# MODUL_GNU-BO_BRIDGE_V101.net
KiCad netlist of a schematic drawn in EAGLE
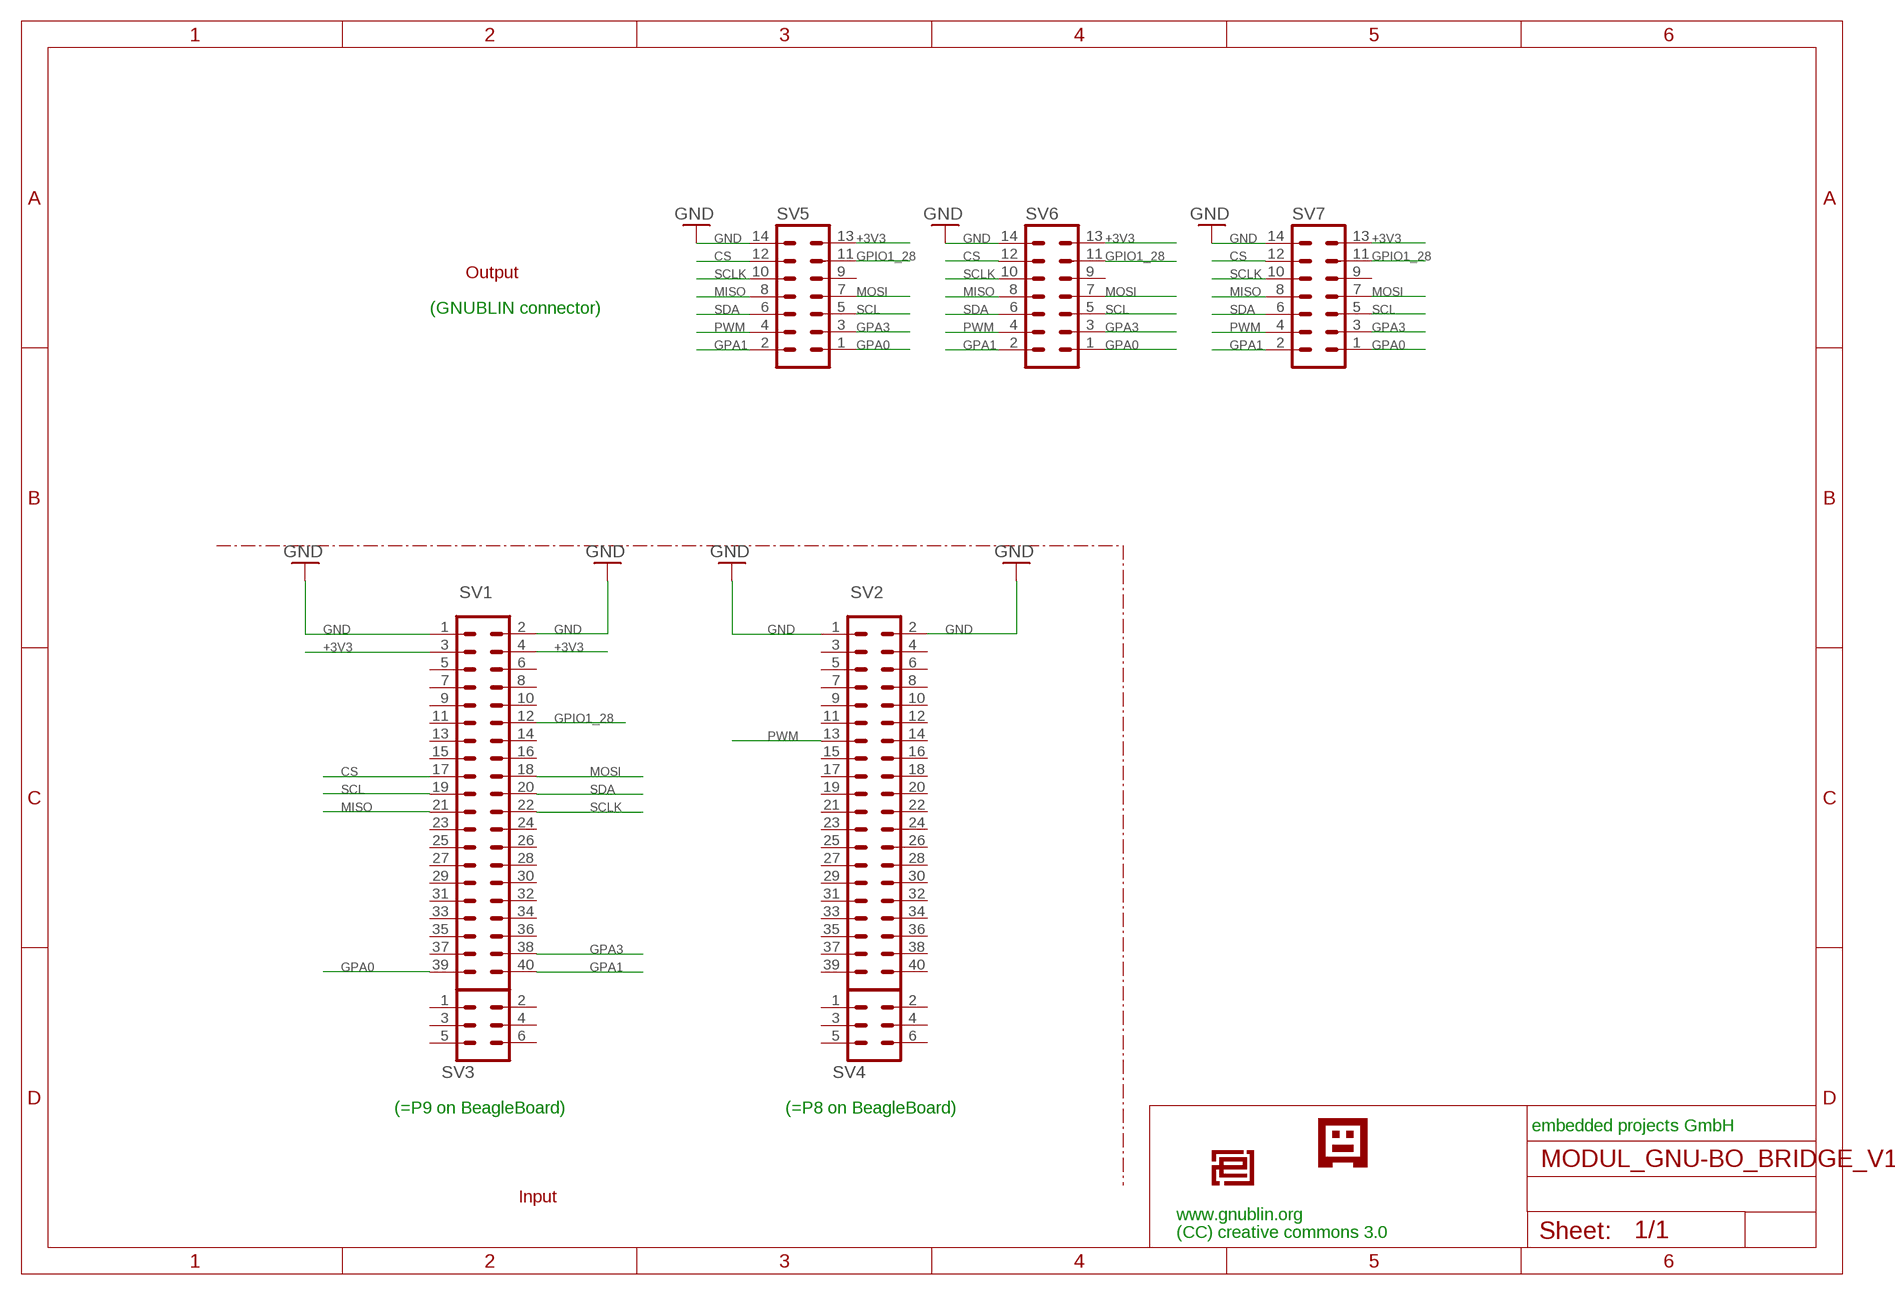
[diagram p0: schematic, sheet 1]

(export (version "E")
  (design (tool "Eeschema 10.0.6"))
  (components
    (comp (ref "SV1")
      (value "MA20-2")
      (footprint "eagle-import:MA20-2")
      (libsource (lib "eagle-import") (part "MA20-2"))
    )
    (comp (ref "SV2")
      (value "MA20-2")
      (footprint "eagle-import:MA20-2")
      (libsource (lib "eagle-import") (part "MA20-2"))
    )
    (comp (ref "SV3")
      (value "MA03-2")
      (footprint "eagle-import:MA03-2")
      (libsource (lib "eagle-import") (part "MA03-2"))
    )
    (comp (ref "SV4")
      (value "MA03-2")
      (footprint "eagle-import:MA03-2")
      (libsource (lib "eagle-import") (part "MA03-2"))
    )
    (comp (ref "SV5")
      (value "ML14")
      (footprint "eagle-import:ML14")
      (libsource (lib "eagle-import") (part "ML14"))
    )
    (comp (ref "SV6")
      (value "ML14")
      (footprint "eagle-import:ML14")
      (libsource (lib "eagle-import") (part "ML14"))
    )
    (comp (ref "SV7")
      (value "ML14")
      (footprint "eagle-import:ML14")
      (libsource (lib "eagle-import") (part "ML14"))
    )
    (comp (ref "U$2")
      (value "EPLOGOSIEB")
      (footprint "eagle-import:EPLOGOSIEBDRUCK")
      (libsource (lib "eagle-import") (part "EPLOGOSIEB"))
    )
    (comp (ref "U$3")
      (value "GNUBLINLOGOSIEB")
      (footprint "eagle-import:GNUSIEBDRUCK")
      (libsource (lib "eagle-import") (part "GNUBLINLOGOSIEB"))
    )
  )
  (nets
    (net (code "1") (name "/+3V3") (class "Default")
      (node (ref "SV1") (pin "3") (pinfunction "3_3") (pintype "passive"))
      (node (ref "SV1") (pin "4") (pinfunction "4_4") (pintype "passive"))
      (node (ref "SV5") (pin "13") (pinfunction "13_13") (pintype "passive"))
      (node (ref "SV6") (pin "13") (pinfunction "13_13") (pintype "passive"))
      (node (ref "SV7") (pin "13") (pinfunction "13_13") (pintype "passive"))
    )
    (net (code "2") (name "/CS") (class "Default")
      (node (ref "SV1") (pin "17") (pinfunction "17_17") (pintype "passive"))
      (node (ref "SV5") (pin "12") (pinfunction "12_12") (pintype "passive"))
      (node (ref "SV6") (pin "12") (pinfunction "12_12") (pintype "passive"))
      (node (ref "SV7") (pin "12") (pinfunction "12_12") (pintype "passive"))
    )
    (net (code "3") (name "/GPA0") (class "Default")
      (node (ref "SV1") (pin "39") (pinfunction "39_39") (pintype "passive"))
      (node (ref "SV5") (pin "1") (pinfunction "1_1") (pintype "passive"))
      (node (ref "SV6") (pin "1") (pinfunction "1_1") (pintype "passive"))
      (node (ref "SV7") (pin "1") (pinfunction "1_1") (pintype "passive"))
    )
    (net (code "4") (name "/GPA1") (class "Default")
      (node (ref "SV1") (pin "40") (pinfunction "40_40") (pintype "passive"))
      (node (ref "SV5") (pin "2") (pinfunction "2_2") (pintype "passive"))
      (node (ref "SV6") (pin "2") (pinfunction "2_2") (pintype "passive"))
      (node (ref "SV7") (pin "2") (pinfunction "2_2") (pintype "passive"))
    )
    (net (code "5") (name "/GPA3") (class "Default")
      (node (ref "SV1") (pin "38") (pinfunction "38_38") (pintype "passive"))
      (node (ref "SV5") (pin "3") (pinfunction "3_3") (pintype "passive"))
      (node (ref "SV6") (pin "3") (pinfunction "3_3") (pintype "passive"))
      (node (ref "SV7") (pin "3") (pinfunction "3_3") (pintype "passive"))
    )
    (net (code "6") (name "/GPIO1_28") (class "Default")
      (node (ref "SV1") (pin "12") (pinfunction "12_12") (pintype "passive"))
      (node (ref "SV5") (pin "11") (pinfunction "11_11") (pintype "passive"))
      (node (ref "SV6") (pin "11") (pinfunction "11_11") (pintype "passive"))
      (node (ref "SV7") (pin "11") (pinfunction "11_11") (pintype "passive"))
    )
    (net (code "7") (name "/MISO") (class "Default")
      (node (ref "SV1") (pin "21") (pinfunction "21_21") (pintype "passive"))
      (node (ref "SV5") (pin "8") (pinfunction "8_8") (pintype "passive"))
      (node (ref "SV6") (pin "8") (pinfunction "8_8") (pintype "passive"))
      (node (ref "SV7") (pin "8") (pinfunction "8_8") (pintype "passive"))
    )
    (net (code "8") (name "/MOSI") (class "Default")
      (node (ref "SV1") (pin "18") (pinfunction "18_18") (pintype "passive"))
      (node (ref "SV5") (pin "7") (pinfunction "7_7") (pintype "passive"))
      (node (ref "SV6") (pin "7") (pinfunction "7_7") (pintype "passive"))
      (node (ref "SV7") (pin "7") (pinfunction "7_7") (pintype "passive"))
    )
    (net (code "9") (name "/PWM") (class "Default")
      (node (ref "SV2") (pin "13") (pinfunction "13_13") (pintype "passive"))
      (node (ref "SV5") (pin "4") (pinfunction "4_4") (pintype "passive"))
      (node (ref "SV6") (pin "4") (pinfunction "4_4") (pintype "passive"))
      (node (ref "SV7") (pin "4") (pinfunction "4_4") (pintype "passive"))
    )
    (net (code "10") (name "/SCL") (class "Default")
      (node (ref "SV1") (pin "19") (pinfunction "19_19") (pintype "passive"))
      (node (ref "SV5") (pin "5") (pinfunction "5_5") (pintype "passive"))
      (node (ref "SV6") (pin "5") (pinfunction "5_5") (pintype "passive"))
      (node (ref "SV7") (pin "5") (pinfunction "5_5") (pintype "passive"))
    )
    (net (code "11") (name "/SCLK") (class "Default")
      (node (ref "SV1") (pin "22") (pinfunction "22_22") (pintype "passive"))
      (node (ref "SV5") (pin "10") (pinfunction "10_10") (pintype "passive"))
      (node (ref "SV6") (pin "10") (pinfunction "10_10") (pintype "passive"))
      (node (ref "SV7") (pin "10") (pinfunction "10_10") (pintype "passive"))
    )
    (net (code "12") (name "/SDA") (class "Default")
      (node (ref "SV1") (pin "20") (pinfunction "20_20") (pintype "passive"))
      (node (ref "SV5") (pin "6") (pinfunction "6_6") (pintype "passive"))
      (node (ref "SV6") (pin "6") (pinfunction "6_6") (pintype "passive"))
      (node (ref "SV7") (pin "6") (pinfunction "6_6") (pintype "passive"))
    )
    (net (code "13") (name "GND") (class "Default")
      (node (ref "SV1") (pin "1") (pinfunction "1_1") (pintype "passive"))
      (node (ref "SV1") (pin "2") (pinfunction "2_2") (pintype "passive"))
      (node (ref "SV2") (pin "1") (pinfunction "1_1") (pintype "passive"))
      (node (ref "SV2") (pin "2") (pinfunction "2_2") (pintype "passive"))
      (node (ref "SV5") (pin "14") (pinfunction "14_14") (pintype "passive"))
      (node (ref "SV6") (pin "14") (pinfunction "14_14") (pintype "passive"))
      (node (ref "SV7") (pin "14") (pinfunction "14_14") (pintype "passive"))
    )
    (net (code "14") (name "unconnected-(SV1-Pad5)") (class "Default")
      (node (ref "SV1") (pin "5") (pinfunction "5_5") (pintype "passive"))
    )
    (net (code "15") (name "unconnected-(SV1-Pad6)") (class "Default")
      (node (ref "SV1") (pin "6") (pinfunction "6_6") (pintype "passive"))
    )
    (net (code "16") (name "unconnected-(SV1-Pad7)") (class "Default")
      (node (ref "SV1") (pin "7") (pinfunction "7_7") (pintype "passive"))
    )
    (net (code "17") (name "unconnected-(SV1-Pad8)") (class "Default")
      (node (ref "SV1") (pin "8") (pinfunction "8_8") (pintype "passive"))
    )
    (net (code "18") (name "unconnected-(SV1-Pad9)") (class "Default")
      (node (ref "SV1") (pin "9") (pinfunction "9_9") (pintype "passive"))
    )
    (net (code "19") (name "unconnected-(SV1-Pad10)") (class "Default")
      (node (ref "SV1") (pin "10") (pinfunction "10_10") (pintype "passive"))
    )
    (net (code "20") (name "unconnected-(SV1-Pad11)") (class "Default")
      (node (ref "SV1") (pin "11") (pinfunction "11_11") (pintype "passive"))
    )
    (net (code "21") (name "unconnected-(SV1-Pad13)") (class "Default")
      (node (ref "SV1") (pin "13") (pinfunction "13_13") (pintype "passive"))
    )
    (net (code "22") (name "unconnected-(SV1-Pad14)") (class "Default")
      (node (ref "SV1") (pin "14") (pinfunction "14_14") (pintype "passive"))
    )
    (net (code "23") (name "unconnected-(SV1-Pad15)") (class "Default")
      (node (ref "SV1") (pin "15") (pinfunction "15_15") (pintype "passive"))
    )
    (net (code "24") (name "unconnected-(SV1-Pad16)") (class "Default")
      (node (ref "SV1") (pin "16") (pinfunction "16_16") (pintype "passive"))
    )
    (net (code "25") (name "unconnected-(SV1-Pad23)") (class "Default")
      (node (ref "SV1") (pin "23") (pinfunction "23_23") (pintype "passive"))
    )
    (net (code "26") (name "unconnected-(SV1-Pad24)") (class "Default")
      (node (ref "SV1") (pin "24") (pinfunction "24_24") (pintype "passive"))
    )
    (net (code "27") (name "unconnected-(SV1-Pad25)") (class "Default")
      (node (ref "SV1") (pin "25") (pinfunction "25_25") (pintype "passive"))
    )
    (net (code "28") (name "unconnected-(SV1-Pad26)") (class "Default")
      (node (ref "SV1") (pin "26") (pinfunction "26_26") (pintype "passive"))
    )
    (net (code "29") (name "unconnected-(SV1-Pad27)") (class "Default")
      (node (ref "SV1") (pin "27") (pinfunction "27_27") (pintype "passive"))
    )
    (net (code "30") (name "unconnected-(SV1-Pad28)") (class "Default")
      (node (ref "SV1") (pin "28") (pinfunction "28_28") (pintype "passive"))
    )
    (net (code "31") (name "unconnected-(SV1-Pad29)") (class "Default")
      (node (ref "SV1") (pin "29") (pinfunction "29_29") (pintype "passive"))
    )
    (net (code "32") (name "unconnected-(SV1-Pad30)") (class "Default")
      (node (ref "SV1") (pin "30") (pinfunction "30_30") (pintype "passive"))
    )
    (net (code "33") (name "unconnected-(SV1-Pad31)") (class "Default")
      (node (ref "SV1") (pin "31") (pinfunction "31_31") (pintype "passive"))
    )
    (net (code "34") (name "unconnected-(SV1-Pad32)") (class "Default")
      (node (ref "SV1") (pin "32") (pinfunction "32_32") (pintype "passive"))
    )
    (net (code "35") (name "unconnected-(SV1-Pad33)") (class "Default")
      (node (ref "SV1") (pin "33") (pinfunction "33_33") (pintype "passive"))
    )
    (net (code "36") (name "unconnected-(SV1-Pad34)") (class "Default")
      (node (ref "SV1") (pin "34") (pinfunction "34_34") (pintype "passive"))
    )
    (net (code "37") (name "unconnected-(SV1-Pad35)") (class "Default")
      (node (ref "SV1") (pin "35") (pinfunction "35_35") (pintype "passive"))
    )
    (net (code "38") (name "unconnected-(SV1-Pad36)") (class "Default")
      (node (ref "SV1") (pin "36") (pinfunction "36_36") (pintype "passive"))
    )
    (net (code "39") (name "unconnected-(SV1-Pad37)") (class "Default")
      (node (ref "SV1") (pin "37") (pinfunction "37_37") (pintype "passive"))
    )
    (net (code "40") (name "unconnected-(SV2-Pad3)") (class "Default")
      (node (ref "SV2") (pin "3") (pinfunction "3_3") (pintype "passive"))
    )
    (net (code "41") (name "unconnected-(SV2-Pad4)") (class "Default")
      (node (ref "SV2") (pin "4") (pinfunction "4_4") (pintype "passive"))
    )
    (net (code "42") (name "unconnected-(SV2-Pad5)") (class "Default")
      (node (ref "SV2") (pin "5") (pinfunction "5_5") (pintype "passive"))
    )
    (net (code "43") (name "unconnected-(SV2-Pad6)") (class "Default")
      (node (ref "SV2") (pin "6") (pinfunction "6_6") (pintype "passive"))
    )
    (net (code "44") (name "unconnected-(SV2-Pad7)") (class "Default")
      (node (ref "SV2") (pin "7") (pinfunction "7_7") (pintype "passive"))
    )
    (net (code "45") (name "unconnected-(SV2-Pad8)") (class "Default")
      (node (ref "SV2") (pin "8") (pinfunction "8_8") (pintype "passive"))
    )
    (net (code "46") (name "unconnected-(SV2-Pad9)") (class "Default")
      (node (ref "SV2") (pin "9") (pinfunction "9_9") (pintype "passive"))
    )
    (net (code "47") (name "unconnected-(SV2-Pad10)") (class "Default")
      (node (ref "SV2") (pin "10") (pinfunction "10_10") (pintype "passive"))
    )
    (net (code "48") (name "unconnected-(SV2-Pad11)") (class "Default")
      (node (ref "SV2") (pin "11") (pinfunction "11_11") (pintype "passive"))
    )
    (net (code "49") (name "unconnected-(SV2-Pad12)") (class "Default")
      (node (ref "SV2") (pin "12") (pinfunction "12_12") (pintype "passive"))
    )
    (net (code "50") (name "unconnected-(SV2-Pad14)") (class "Default")
      (node (ref "SV2") (pin "14") (pinfunction "14_14") (pintype "passive"))
    )
    (net (code "51") (name "unconnected-(SV2-Pad15)") (class "Default")
      (node (ref "SV2") (pin "15") (pinfunction "15_15") (pintype "passive"))
    )
    (net (code "52") (name "unconnected-(SV2-Pad16)") (class "Default")
      (node (ref "SV2") (pin "16") (pinfunction "16_16") (pintype "passive"))
    )
    (net (code "53") (name "unconnected-(SV2-Pad17)") (class "Default")
      (node (ref "SV2") (pin "17") (pinfunction "17_17") (pintype "passive"))
    )
    (net (code "54") (name "unconnected-(SV2-Pad18)") (class "Default")
      (node (ref "SV2") (pin "18") (pinfunction "18_18") (pintype "passive"))
    )
    (net (code "55") (name "unconnected-(SV2-Pad19)") (class "Default")
      (node (ref "SV2") (pin "19") (pinfunction "19_19") (pintype "passive"))
    )
    (net (code "56") (name "unconnected-(SV2-Pad20)") (class "Default")
      (node (ref "SV2") (pin "20") (pinfunction "20_20") (pintype "passive"))
    )
    (net (code "57") (name "unconnected-(SV2-Pad21)") (class "Default")
      (node (ref "SV2") (pin "21") (pinfunction "21_21") (pintype "passive"))
    )
    (net (code "58") (name "unconnected-(SV2-Pad22)") (class "Default")
      (node (ref "SV2") (pin "22") (pinfunction "22_22") (pintype "passive"))
    )
    (net (code "59") (name "unconnected-(SV2-Pad23)") (class "Default")
      (node (ref "SV2") (pin "23") (pinfunction "23_23") (pintype "passive"))
    )
    (net (code "60") (name "unconnected-(SV2-Pad24)") (class "Default")
      (node (ref "SV2") (pin "24") (pinfunction "24_24") (pintype "passive"))
    )
    (net (code "61") (name "unconnected-(SV2-Pad25)") (class "Default")
      (node (ref "SV2") (pin "25") (pinfunction "25_25") (pintype "passive"))
    )
    (net (code "62") (name "unconnected-(SV2-Pad26)") (class "Default")
      (node (ref "SV2") (pin "26") (pinfunction "26_26") (pintype "passive"))
    )
    (net (code "63") (name "unconnected-(SV2-Pad27)") (class "Default")
      (node (ref "SV2") (pin "27") (pinfunction "27_27") (pintype "passive"))
    )
    (net (code "64") (name "unconnected-(SV2-Pad28)") (class "Default")
      (node (ref "SV2") (pin "28") (pinfunction "28_28") (pintype "passive"))
    )
    (net (code "65") (name "unconnected-(SV2-Pad29)") (class "Default")
      (node (ref "SV2") (pin "29") (pinfunction "29_29") (pintype "passive"))
    )
    (net (code "66") (name "unconnected-(SV2-Pad30)") (class "Default")
      (node (ref "SV2") (pin "30") (pinfunction "30_30") (pintype "passive"))
    )
    (net (code "67") (name "unconnected-(SV2-Pad31)") (class "Default")
      (node (ref "SV2") (pin "31") (pinfunction "31_31") (pintype "passive"))
    )
    (net (code "68") (name "unconnected-(SV2-Pad32)") (class "Default")
      (node (ref "SV2") (pin "32") (pinfunction "32_32") (pintype "passive"))
    )
    (net (code "69") (name "unconnected-(SV2-Pad33)") (class "Default")
      (node (ref "SV2") (pin "33") (pinfunction "33_33") (pintype "passive"))
    )
    (net (code "70") (name "unconnected-(SV2-Pad34)") (class "Default")
      (node (ref "SV2") (pin "34") (pinfunction "34_34") (pintype "passive"))
    )
    (net (code "71") (name "unconnected-(SV2-Pad35)") (class "Default")
      (node (ref "SV2") (pin "35") (pinfunction "35_35") (pintype "passive"))
    )
    (net (code "72") (name "unconnected-(SV2-Pad36)") (class "Default")
      (node (ref "SV2") (pin "36") (pinfunction "36_36") (pintype "passive"))
    )
    (net (code "73") (name "unconnected-(SV2-Pad37)") (class "Default")
      (node (ref "SV2") (pin "37") (pinfunction "37_37") (pintype "passive"))
    )
    (net (code "74") (name "unconnected-(SV2-Pad38)") (class "Default")
      (node (ref "SV2") (pin "38") (pinfunction "38_38") (pintype "passive"))
    )
    (net (code "75") (name "unconnected-(SV2-Pad39)") (class "Default")
      (node (ref "SV2") (pin "39") (pinfunction "39_39") (pintype "passive"))
    )
    (net (code "76") (name "unconnected-(SV2-Pad40)") (class "Default")
      (node (ref "SV2") (pin "40") (pinfunction "40_40") (pintype "passive"))
    )
    (net (code "77") (name "unconnected-(SV3-Pad1)") (class "Default")
      (node (ref "SV3") (pin "1") (pinfunction "1_1") (pintype "passive"))
    )
    (net (code "78") (name "unconnected-(SV3-Pad2)") (class "Default")
      (node (ref "SV3") (pin "2") (pinfunction "2_2") (pintype "passive"))
    )
    (net (code "79") (name "unconnected-(SV3-Pad3)") (class "Default")
      (node (ref "SV3") (pin "3") (pinfunction "3_3") (pintype "passive"))
    )
    (net (code "80") (name "unconnected-(SV3-Pad4)") (class "Default")
      (node (ref "SV3") (pin "4") (pinfunction "4_4") (pintype "passive"))
    )
    (net (code "81") (name "unconnected-(SV3-Pad5)") (class "Default")
      (node (ref "SV3") (pin "5") (pinfunction "5_5") (pintype "passive"))
    )
    (net (code "82") (name "unconnected-(SV3-Pad6)") (class "Default")
      (node (ref "SV3") (pin "6") (pinfunction "6_6") (pintype "passive"))
    )
    (net (code "83") (name "unconnected-(SV4-Pad1)") (class "Default")
      (node (ref "SV4") (pin "1") (pinfunction "1_1") (pintype "passive"))
    )
    (net (code "84") (name "unconnected-(SV4-Pad2)") (class "Default")
      (node (ref "SV4") (pin "2") (pinfunction "2_2") (pintype "passive"))
    )
    (net (code "85") (name "unconnected-(SV4-Pad3)") (class "Default")
      (node (ref "SV4") (pin "3") (pinfunction "3_3") (pintype "passive"))
    )
    (net (code "86") (name "unconnected-(SV4-Pad4)") (class "Default")
      (node (ref "SV4") (pin "4") (pinfunction "4_4") (pintype "passive"))
    )
    (net (code "87") (name "unconnected-(SV4-Pad5)") (class "Default")
      (node (ref "SV4") (pin "5") (pinfunction "5_5") (pintype "passive"))
    )
    (net (code "88") (name "unconnected-(SV4-Pad6)") (class "Default")
      (node (ref "SV4") (pin "6") (pinfunction "6_6") (pintype "passive"))
    )
    (net (code "89") (name "unconnected-(SV5-Pad9)") (class "Default")
      (node (ref "SV5") (pin "9") (pinfunction "9_9") (pintype "passive"))
    )
    (net (code "90") (name "unconnected-(SV6-Pad9)") (class "Default")
      (node (ref "SV6") (pin "9") (pinfunction "9_9") (pintype "passive"))
    )
    (net (code "91") (name "unconnected-(SV7-Pad9)") (class "Default")
      (node (ref "SV7") (pin "9") (pinfunction "9_9") (pintype "passive"))
    )
  )
)
